# 1-Schematic_ISMWAVER315_MODULE.net
KiCad netlist of a schematic drawn in EasyEDA
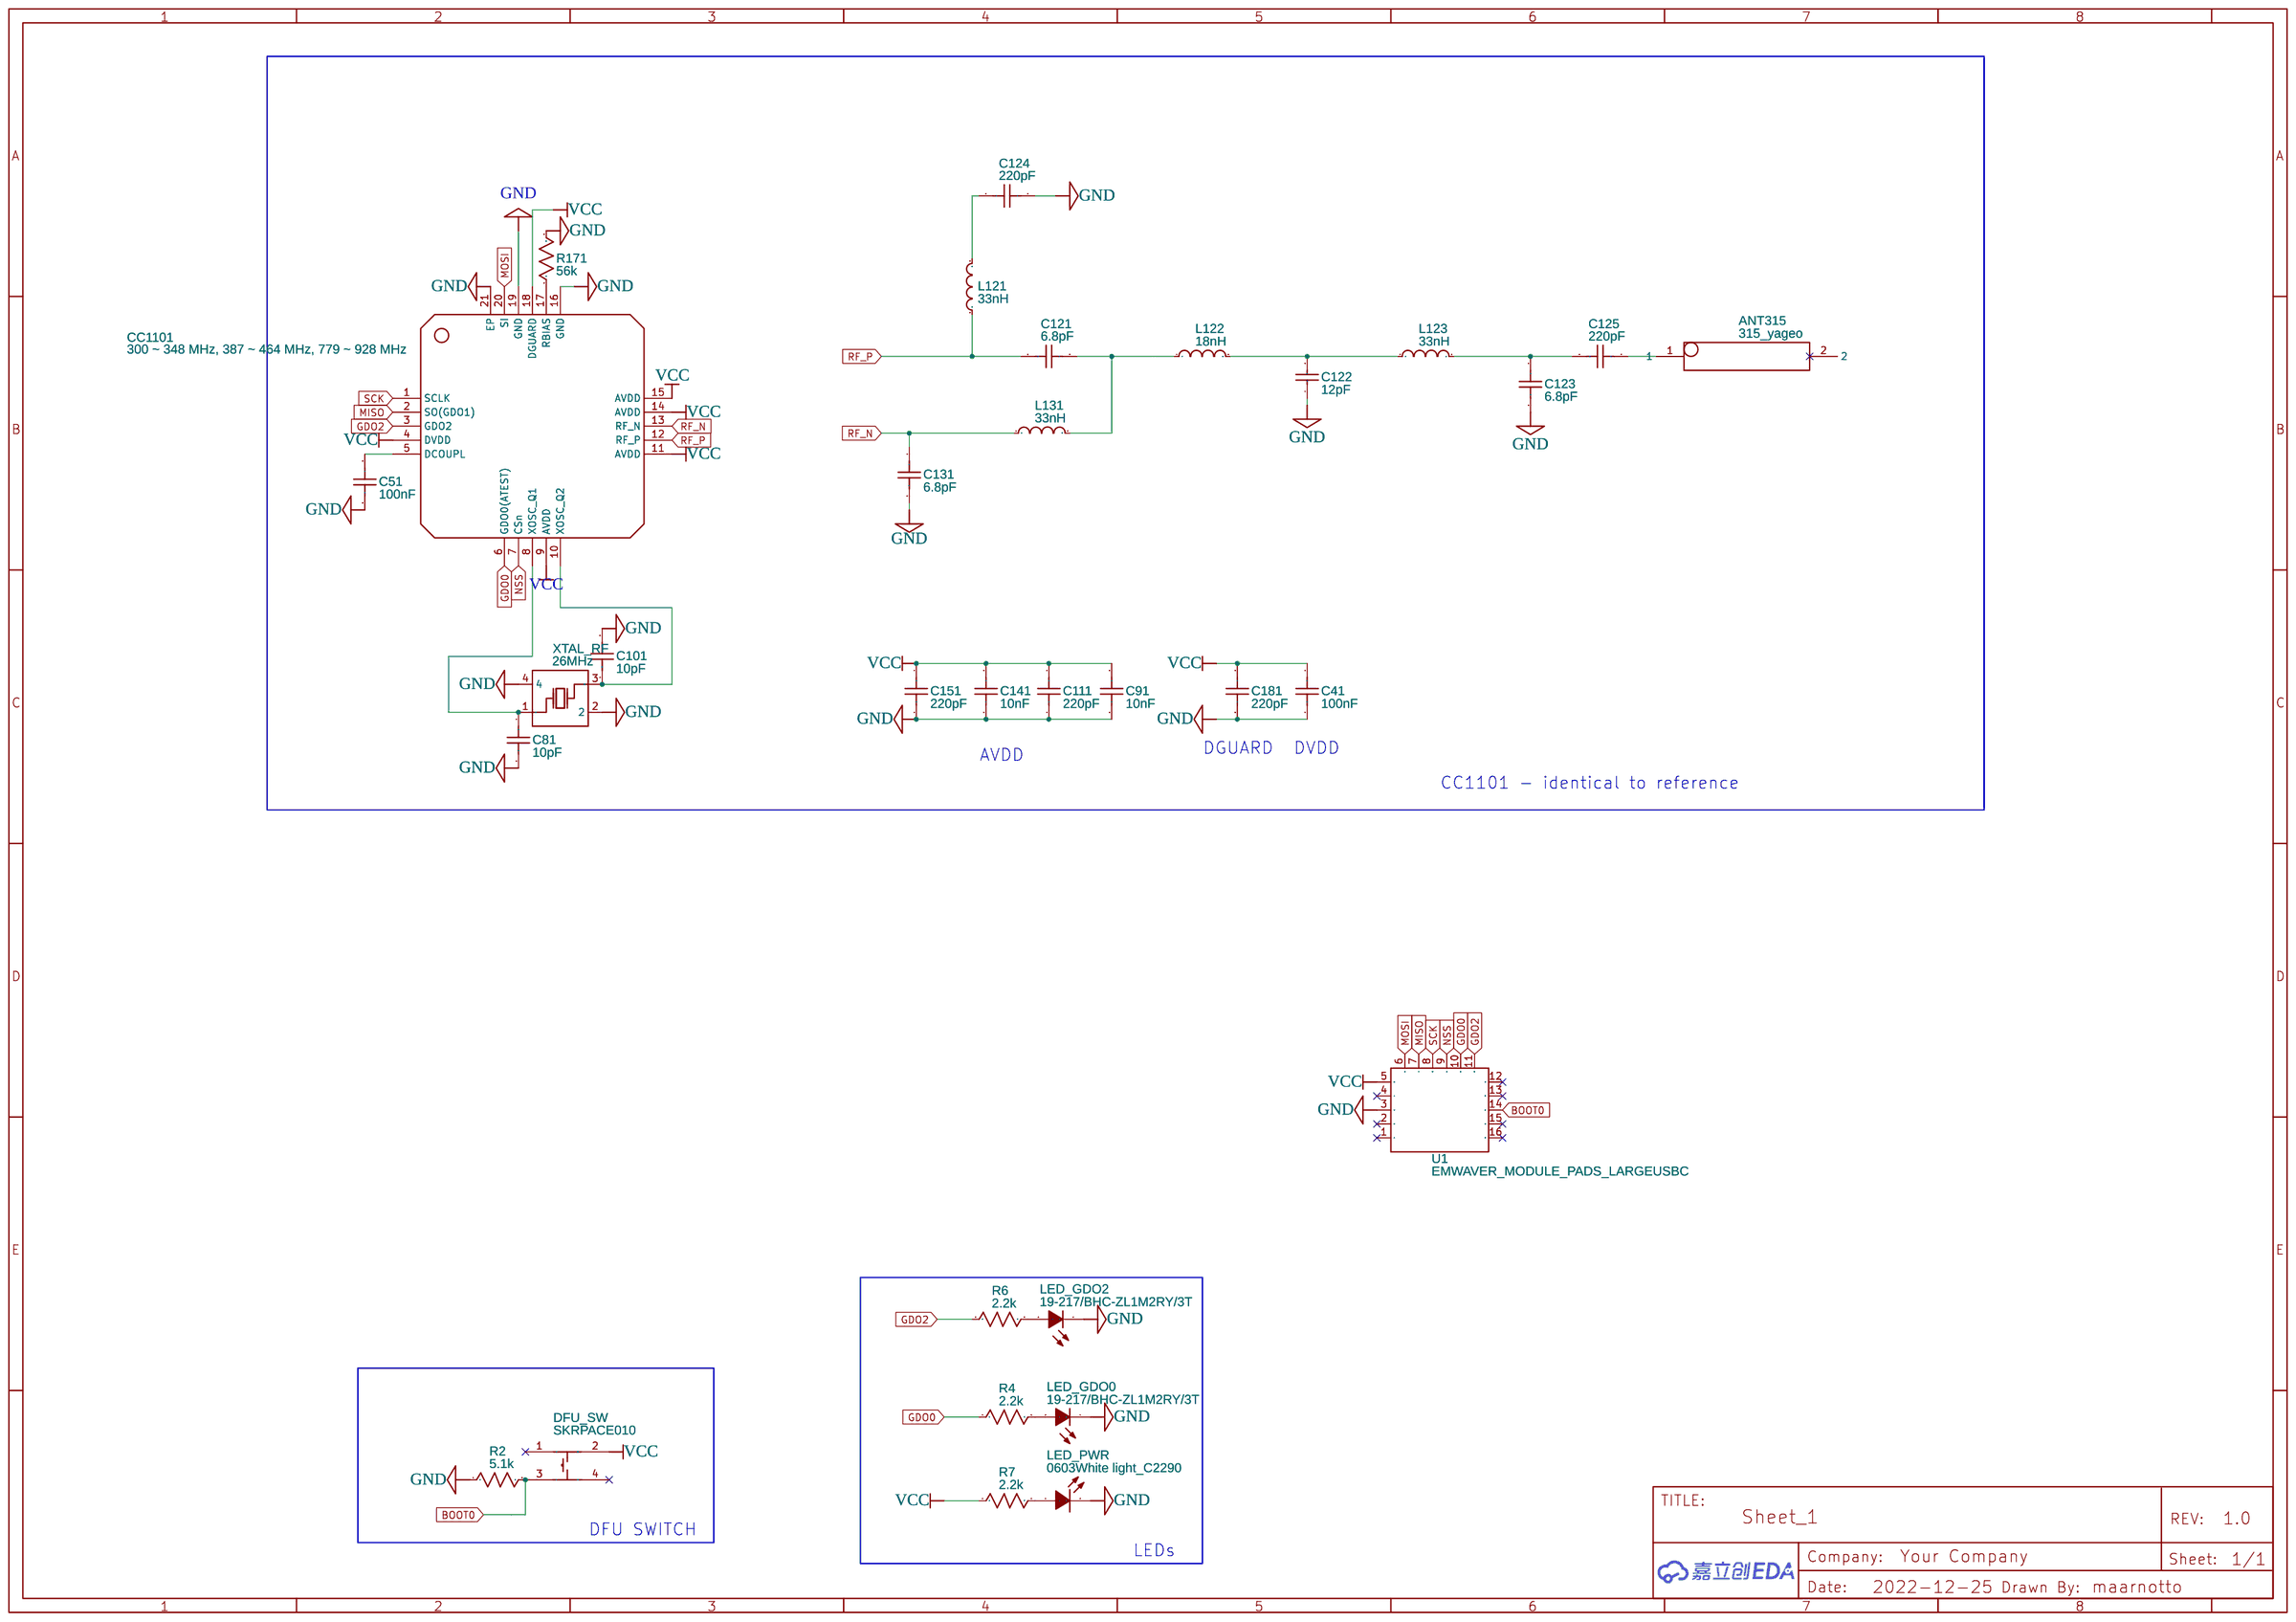
[diagram p0: schematic sheet]

(export (version "E")
  (design (tool "Eeschema 10.0.6"))
  (components
    (comp (ref "ANT315")
      (value "315_yageo")
      (fields
        (field (name "Manufacturer Part") "ANT1204F002R0315A")
        (field (name "Manufacturer") "PULSE ELECTRONICS")
      )
      (libsource (lib "") (part "315_yageo"))
    )
    (comp (ref "C41") (value "100nF") (libsource (lib "") (part "C_0402_US")))
    (comp (ref "C51") (value "100nF") (libsource (lib "") (part "C_0402_US")))
    (comp (ref "C81") (value "10pF") (libsource (lib "") (part "C_0402_US")))
    (comp (ref "C91") (value "10nF") (libsource (lib "") (part "C_0402_US")))
    (comp (ref "C101") (value "10pF") (libsource (lib "") (part "C_0402_US_1")))
    (comp (ref "C111") (value "220pF") (libsource (lib "") (part "C_0402_US")))
    (comp (ref "C121") (value "6.8pF") (libsource (lib "") (part "C_0402_US_2")))
    (comp (ref "C122")
      (value "12pF")
      (fields (field (name "Manufacturer Part") "0402CG8R2C500NT") (field (name "Manufacturer") "FH(风华)"))
      (libsource (lib "") (part "0402CG8R2C500NT"))
    )
    (comp (ref "C123") (value "6.8pF") (libsource (lib "") (part "C_0402_US")))
    (comp (ref "C124") (value "220pF") (libsource (lib "") (part "C_0402_US_2")))
    (comp (ref "C125") (value "220pF") (libsource (lib "") (part "C_0402_US_2")))
    (comp (ref "C131") (value "6.8pF") (libsource (lib "") (part "C_0402_US")))
    (comp (ref "C141") (value "10nF") (libsource (lib "") (part "C_0402_US")))
    (comp (ref "C151") (value "220pF") (libsource (lib "") (part "C_0402_US")))
    (comp (ref "C181") (value "220pF") (libsource (lib "") (part "C_0402_US")))
    (comp (ref "CC1101")
      (value "300 ~ 348 MHz, 387 ~ 464 MHz, 779 ~ 928 MHz")
      (fields (field (name "Manufacturer Part") "CC1101RGPR") (field (name "Manufacturer") "TI(德州仪器)"))
      (libsource (lib "") (part "CC1101RGPR"))
    )
    (comp (ref "DFU_SW")
      (value "SKRPACE010")
      (fields (field (name "Manufacturer") "ALPSALPINE(阿尔卑斯阿尔派)"))
      (libsource (lib "") (part "SKRPACE010"))
    )
    (comp (ref "L121") (value "33nH") (libsource (lib "") (part "L0402_US_1")))
    (comp (ref "L122") (value "18nH") (libsource (lib "") (part "L0402_US")))
    (comp (ref "L123") (value "33nH") (libsource (lib "") (part "L0402_US")))
    (comp (ref "L131") (value "33nH") (libsource (lib "") (part "L0402_US")))
    (comp (ref "LED_GDO0")
      (value "19-217/BHC-ZL1M2RY/3T")
      (fields (field (name "Manufacturer") "EVERLIGHT(亿光)"))
      (libsource (lib "") (part "19-217/BHC-ZL1M2RY/3T"))
    )
    (comp (ref "LED_GDO2")
      (value "19-217/BHC-ZL1M2RY/3T")
      (fields (field (name "Manufacturer") "EVERLIGHT(亿光)"))
      (libsource (lib "") (part "19-217/BHC-ZL1M2RY/3T"))
    )
    (comp (ref "LED_PWR")
      (value "0603White light_C2290")
      (fields (field (name "Manufacturer Part") "KT-0603白灯"))
      (libsource (lib "") (part "0603White light_C2290"))
    )
    (comp (ref "R2") (value "5.1k") (libsource (lib "") (part "R_0603_US")))
    (comp (ref "R4") (value "2.2k") (libsource (lib "") (part "R_0603_US")))
    (comp (ref "R6") (value "2.2k") (libsource (lib "") (part "R_0603_US")))
    (comp (ref "R7") (value "2.2k") (libsource (lib "") (part "R_0603_US")))
    (comp (ref "R171") (value "56k") (libsource (lib "") (part "R_0402_US")))
    (comp (ref "U1")
      (value "EMWAVER_MODULE_PADS_LARGEUSBC")
      (libsource (lib "") (part "EMWAVER_MODULE_PADS_LARGEUSBC"))
    )
    (comp (ref "XTAL_RF")
      (value "26MHz")
      (fields (field (name "Manufacturer Part") "3S26000333") (field (name "Manufacturer") "YL(惠伦晶体)"))
      (libsource (lib "") (part "3S26000333"))
    )
  )
  (nets
    (net (code "1") (name "BOOT0") (class "Default")
      (node (ref "DFU_SW") (pin "3") (pinfunction "3_3") (pintype "unspecified"))
      (node (ref "R2") (pin "2") (pinfunction "2_2") (pintype "unspecified"))
      (node (ref "U1") (pin "14") (pinfunction "14_14") (pintype "unspecified"))
    )
    (net (code "2") (name "GDO0") (class "Default")
      (node (ref "CC1101") (pin "6") (pinfunction "GDO0(ATEST)_6") (pintype "unspecified"))
      (node (ref "R4") (pin "1") (pinfunction "1_1") (pintype "unspecified"))
      (node (ref "U1") (pin "10") (pinfunction "10_10") (pintype "unspecified"))
    )
    (net (code "3") (name "GDO2") (class "Default")
      (node (ref "CC1101") (pin "3") (pinfunction "GDO2_3") (pintype "unspecified"))
      (node (ref "R6") (pin "1") (pinfunction "1_1") (pintype "unspecified"))
      (node (ref "U1") (pin "11") (pinfunction "11_11") (pintype "unspecified"))
    )
    (net (code "4") (name "GND") (class "Default")
      (node (ref "C101") (pin "2") (pinfunction "2_2") (pintype "unspecified"))
      (node (ref "C111") (pin "2") (pinfunction "2_2") (pintype "unspecified"))
      (node (ref "C122") (pin "1") (pinfunction "1_1") (pintype "input"))
      (node (ref "C123") (pin "2") (pinfunction "2_2") (pintype "unspecified"))
      (node (ref "C124") (pin "1") (pinfunction "1_1") (pintype "unspecified"))
      (node (ref "C131") (pin "2") (pinfunction "2_2") (pintype "unspecified"))
      (node (ref "C141") (pin "2") (pinfunction "2_2") (pintype "unspecified"))
      (node (ref "C151") (pin "2") (pinfunction "2_2") (pintype "unspecified"))
      (node (ref "C181") (pin "2") (pinfunction "2_2") (pintype "unspecified"))
      (node (ref "C41") (pin "2") (pinfunction "2_2") (pintype "unspecified"))
      (node (ref "C51") (pin "2") (pinfunction "2_2") (pintype "unspecified"))
      (node (ref "C81") (pin "2") (pinfunction "2_2") (pintype "unspecified"))
      (node (ref "C91") (pin "2") (pinfunction "2_2") (pintype "unspecified"))
      (node (ref "CC1101") (pin "16") (pinfunction "GND_16") (pintype "unspecified"))
      (node (ref "CC1101") (pin "19") (pinfunction "GND_19") (pintype "unspecified"))
      (node (ref "CC1101") (pin "21") (pinfunction "EP_21") (pintype "unspecified"))
      (node (ref "LED_GDO0") (pin "1") (pinfunction "C_1") (pintype "input"))
      (node (ref "LED_GDO2") (pin "1") (pinfunction "C_1") (pintype "input"))
      (node (ref "LED_PWR") (pin "2") (pinfunction "K_2") (pintype "unspecified"))
      (node (ref "R171") (pin "2") (pinfunction "2_2") (pintype "unspecified"))
      (node (ref "R2") (pin "1") (pinfunction "1_1") (pintype "unspecified"))
      (node (ref "U1") (pin "3") (pinfunction "3_3") (pintype "unspecified"))
      (node (ref "XTAL_RF") (pin "2") (pinfunction "2_2") (pintype "unspecified"))
      (node (ref "XTAL_RF") (pin "4") (pinfunction "4_4") (pintype "unspecified"))
    )
    (net (code "5") (name "MISO") (class "Default")
      (node (ref "CC1101") (pin "2") (pinfunction "SO(GDO1)_2") (pintype "unspecified"))
      (node (ref "U1") (pin "7") (pinfunction "7_7") (pintype "unspecified"))
    )
    (net (code "6") (name "MOSI") (class "Default")
      (node (ref "CC1101") (pin "20") (pinfunction "SI_20") (pintype "unspecified"))
      (node (ref "U1") (pin "6") (pinfunction "6_6") (pintype "unspecified"))
    )
    (net (code "7") (name "NSS") (class "Default")
      (node (ref "CC1101") (pin "7") (pinfunction "CSn_7") (pintype "unspecified"))
      (node (ref "U1") (pin "9") (pinfunction "9_9") (pintype "unspecified"))
    )
    (net (code "8") (name "Net-(ANT315-Pad1)") (class "Default")
      (node (ref "ANT315") (pin "1") (pinfunction "1_1") (pintype "unspecified"))
      (node (ref "C125") (pin "1") (pinfunction "1_1") (pintype "unspecified"))
    )
    (net (code "9") (name "Net-(C121-Pad1)") (class "Default")
      (node (ref "C121") (pin "1") (pinfunction "1_1") (pintype "unspecified"))
      (node (ref "L122") (pin "1") (pinfunction "1_1") (pintype "unspecified"))
      (node (ref "L131") (pin "2") (pinfunction "2_2") (pintype "unspecified"))
    )
    (net (code "10") (name "Net-(C122-Pad2)") (class "Default")
      (node (ref "C122") (pin "2") (pinfunction "2_2") (pintype "input"))
      (node (ref "L122") (pin "2") (pinfunction "2_2") (pintype "unspecified"))
      (node (ref "L123") (pin "1") (pinfunction "1_1") (pintype "unspecified"))
    )
    (net (code "11") (name "Net-(C123-Pad1)") (class "Default")
      (node (ref "C123") (pin "1") (pinfunction "1_1") (pintype "unspecified"))
      (node (ref "C125") (pin "2") (pinfunction "2_2") (pintype "unspecified"))
      (node (ref "L123") (pin "2") (pinfunction "2_2") (pintype "unspecified"))
    )
    (net (code "12") (name "Net-(C124-Pad2)") (class "Default")
      (node (ref "C124") (pin "2") (pinfunction "2_2") (pintype "unspecified"))
      (node (ref "L121") (pin "2") (pinfunction "2_2") (pintype "unspecified"))
    )
    (net (code "13") (name "Net-(CC1101-DCOUPL)") (class "Default")
      (node (ref "C51") (pin "1") (pinfunction "1_1") (pintype "unspecified"))
      (node (ref "CC1101") (pin "5") (pinfunction "DCOUPL_5") (pintype "unspecified"))
    )
    (net (code "14") (name "Net-(CC1101-RBIAS)") (class "Default")
      (node (ref "CC1101") (pin "17") (pinfunction "RBIAS_17") (pintype "unspecified"))
      (node (ref "R171") (pin "1") (pinfunction "1_1") (pintype "unspecified"))
    )
    (net (code "15") (name "Net-(CC1101-XOSC_Q1)") (class "Default")
      (node (ref "C81") (pin "1") (pinfunction "1_1") (pintype "unspecified"))
      (node (ref "CC1101") (pin "8") (pinfunction "XOSC_Q1_8") (pintype "unspecified"))
      (node (ref "XTAL_RF") (pin "1") (pinfunction "OSC1_1") (pintype "unspecified"))
    )
    (net (code "16") (name "Net-(CC1101-XOSC_Q2)") (class "Default")
      (node (ref "C101") (pin "1") (pinfunction "1_1") (pintype "unspecified"))
      (node (ref "CC1101") (pin "10") (pinfunction "XOSC_Q2_10") (pintype "unspecified"))
      (node (ref "XTAL_RF") (pin "3") (pinfunction "OSC2_3") (pintype "unspecified"))
    )
    (net (code "17") (name "Net-(LED_GDO0-A)") (class "Default")
      (node (ref "LED_GDO0") (pin "2") (pinfunction "A_2") (pintype "input"))
      (node (ref "R4") (pin "2") (pinfunction "2_2") (pintype "unspecified"))
    )
    (net (code "18") (name "Net-(LED_GDO2-A)") (class "Default")
      (node (ref "LED_GDO2") (pin "2") (pinfunction "A_2") (pintype "input"))
      (node (ref "R6") (pin "2") (pinfunction "2_2") (pintype "unspecified"))
    )
    (net (code "19") (name "Net-(LED_PWR-A)") (class "Default")
      (node (ref "LED_PWR") (pin "1") (pinfunction "A_1") (pintype "unspecified"))
      (node (ref "R7") (pin "2") (pinfunction "2_2") (pintype "unspecified"))
    )
    (net (code "20") (name "RF_N") (class "Default")
      (node (ref "C131") (pin "1") (pinfunction "1_1") (pintype "unspecified"))
      (node (ref "CC1101") (pin "13") (pinfunction "RF_N_13") (pintype "unspecified"))
      (node (ref "L131") (pin "1") (pinfunction "1_1") (pintype "unspecified"))
    )
    (net (code "21") (name "RF_P") (class "Default")
      (node (ref "C121") (pin "2") (pinfunction "2_2") (pintype "unspecified"))
      (node (ref "CC1101") (pin "12") (pinfunction "RF_P_12") (pintype "unspecified"))
      (node (ref "L121") (pin "1") (pinfunction "1_1") (pintype "unspecified"))
    )
    (net (code "22") (name "SCK") (class "Default")
      (node (ref "CC1101") (pin "1") (pinfunction "SCLK_1") (pintype "unspecified"))
      (node (ref "U1") (pin "8") (pinfunction "8_8") (pintype "unspecified"))
    )
    (net (code "23") (name "VCC") (class "Default")
      (node (ref "C111") (pin "1") (pinfunction "1_1") (pintype "unspecified"))
      (node (ref "C141") (pin "1") (pinfunction "1_1") (pintype "unspecified"))
      (node (ref "C151") (pin "1") (pinfunction "1_1") (pintype "unspecified"))
      (node (ref "C181") (pin "1") (pinfunction "1_1") (pintype "unspecified"))
      (node (ref "C41") (pin "1") (pinfunction "1_1") (pintype "unspecified"))
      (node (ref "C91") (pin "1") (pinfunction "1_1") (pintype "unspecified"))
      (node (ref "CC1101") (pin "11") (pinfunction "AVDD_11") (pintype "unspecified"))
      (node (ref "CC1101") (pin "14") (pinfunction "AVDD_14") (pintype "unspecified"))
      (node (ref "CC1101") (pin "15") (pinfunction "AVDD_15") (pintype "unspecified"))
      (node (ref "CC1101") (pin "18") (pinfunction "DGUARD_18") (pintype "unspecified"))
      (node (ref "CC1101") (pin "4") (pinfunction "DVDD_4") (pintype "unspecified"))
      (node (ref "CC1101") (pin "9") (pinfunction "AVDD_9") (pintype "unspecified"))
      (node (ref "DFU_SW") (pin "2") (pinfunction "2_2") (pintype "unspecified"))
      (node (ref "R7") (pin "1") (pinfunction "1_1") (pintype "unspecified"))
      (node (ref "U1") (pin "5") (pinfunction "5_5") (pintype "unspecified"))
    )
    (net (code "24") (name "unconnected-(ANT315-Pad2)") (class "Default")
      (node (ref "ANT315") (pin "2") (pinfunction "2_2") (pintype "unspecified+no_connect"))
    )
    (net (code "25") (name "unconnected-(DFU_SW-Pad1)") (class "Default")
      (node (ref "DFU_SW") (pin "1") (pinfunction "1_1") (pintype "unspecified+no_connect"))
    )
    (net (code "26") (name "unconnected-(DFU_SW-Pad4)") (class "Default")
      (node (ref "DFU_SW") (pin "4") (pinfunction "4_4") (pintype "unspecified+no_connect"))
    )
    (net (code "27") (name "unconnected-(U1-Pad1)") (class "Default")
      (node (ref "U1") (pin "1") (pinfunction "1_1") (pintype "unspecified+no_connect"))
    )
    (net (code "28") (name "unconnected-(U1-Pad2)") (class "Default")
      (node (ref "U1") (pin "2") (pinfunction "2_2") (pintype "unspecified+no_connect"))
    )
    (net (code "29") (name "unconnected-(U1-Pad4)") (class "Default")
      (node (ref "U1") (pin "4") (pinfunction "4_4") (pintype "unspecified+no_connect"))
    )
    (net (code "30") (name "unconnected-(U1-Pad12)") (class "Default")
      (node (ref "U1") (pin "12") (pinfunction "12_12") (pintype "unspecified+no_connect"))
    )
    (net (code "31") (name "unconnected-(U1-Pad13)") (class "Default")
      (node (ref "U1") (pin "13") (pinfunction "13_13") (pintype "unspecified+no_connect"))
    )
    (net (code "32") (name "unconnected-(U1-Pad15)") (class "Default")
      (node (ref "U1") (pin "15") (pinfunction "15_15") (pintype "unspecified+no_connect"))
    )
    (net (code "33") (name "unconnected-(U1-Pad16)") (class "Default")
      (node (ref "U1") (pin "16") (pinfunction "16_16") (pintype "unspecified+no_connect"))
    )
  )
)
